# OHIS_FT65E.net
KiCad netlist of a schematic drawn in Altium Designer
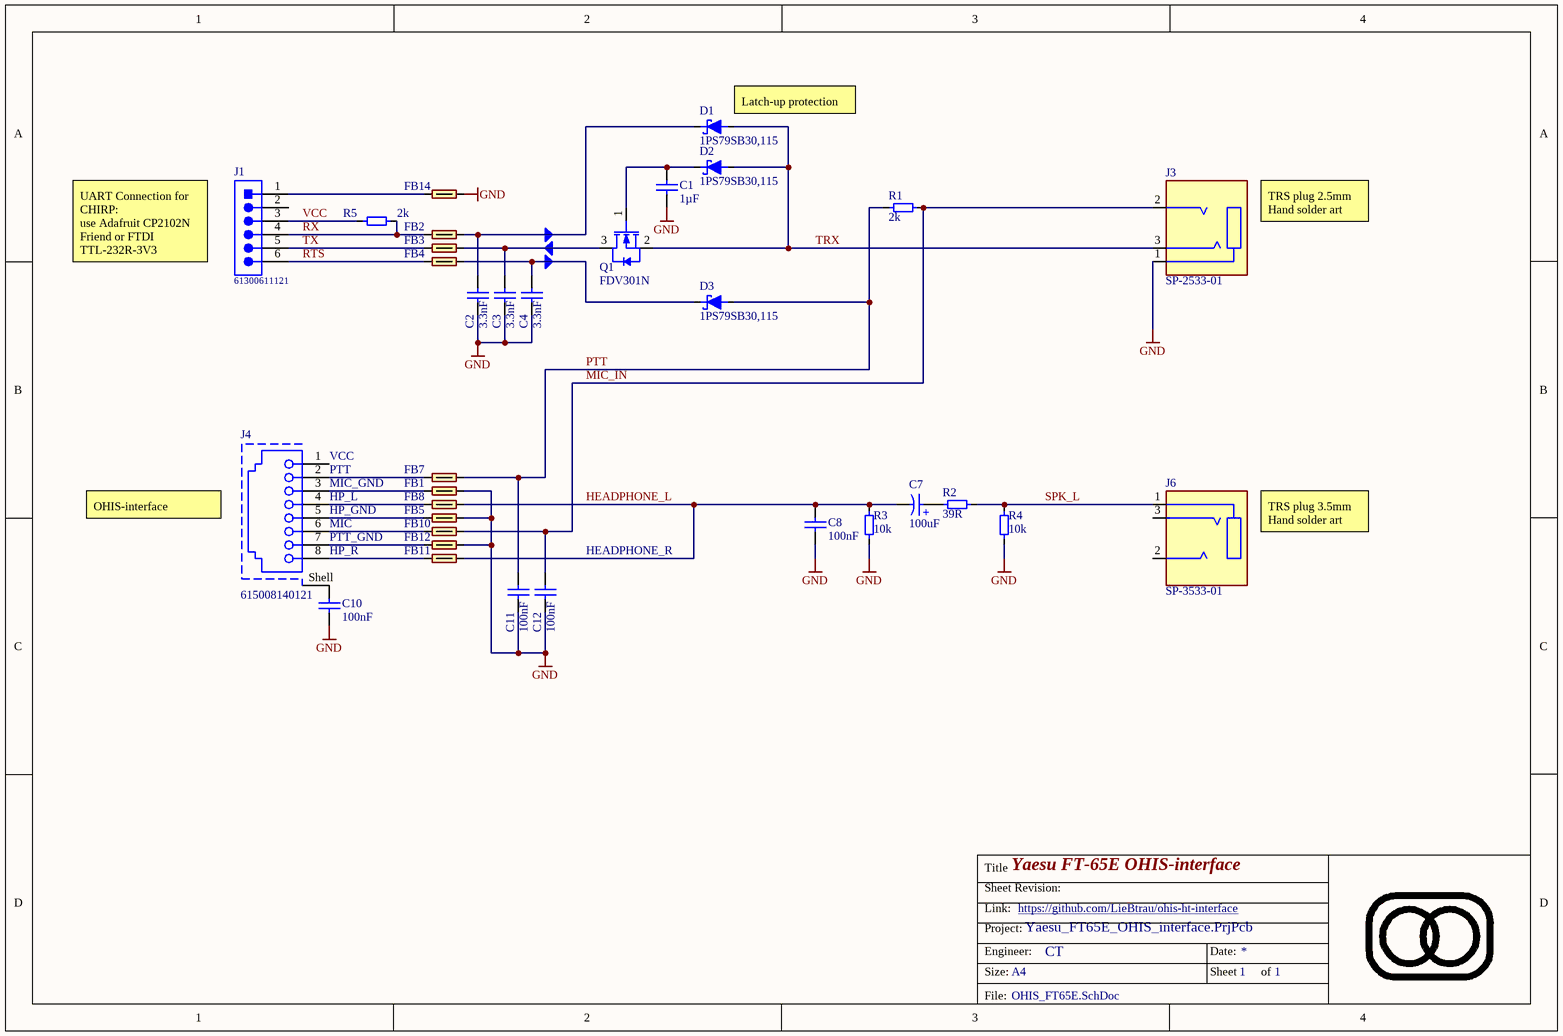
[diagram p0: OHIS_FT65E.SchDoc]

(export (version "E")
  (design (tool "Eeschema 10.0.6"))
  (components
    (comp (ref "C1")
      (value "1µF")
      (footprint "0805-C-N")
      (description "WCAP-CSGP Multilayer Ceramic Chip Capacitor, General Purpose, size 0805, X7R, 1µF, 10VDC")
      (fields (field (name "TOLERANCE") "10%") (field (name "JLCPCB PART #") "C28323"))
      (libsource (lib "7c7 Engineering") (part "CAP-NP-2"))
    )
    (comp (ref "C2")
      (value "3.3nF")
      (footprint "0603-C-N")
      (description "WCAP-CSGP Multilayer Ceramic Chip Capacitor, General Purpose, size 0603, X7R, 3.3nF, 50VDC")
      (fields (field (name "TOLERANCE") "10%") (field (name "Comment") "Capacitor 3.3nF +/-10% 50V X7R 0603"))
      (libsource (lib "7c7 Engineering") (part "CAP-NP-2"))
    )
    (comp (ref "C3")
      (value "3.3nF")
      (footprint "0603-C-N")
      (description "WCAP-CSGP Multilayer Ceramic Chip Capacitor, General Purpose, size 0603, X7R, 3.3nF, 50VDC")
      (fields (field (name "TOLERANCE") "10%") (field (name "Comment") "Capacitor 3.3nF +/-10% 50V X7R 0603"))
      (libsource (lib "7c7 Engineering") (part "CAP-NP-2"))
    )
    (comp (ref "C4")
      (value "3.3nF")
      (footprint "0603-C-N")
      (description "WCAP-CSGP Multilayer Ceramic Chip Capacitor, General Purpose, size 0603, X7R, 3.3nF, 50VDC")
      (fields (field (name "TOLERANCE") "10%") (field (name "Comment") "Capacitor 3.3nF +/-10% 50V X7R 0603"))
      (libsource (lib "7c7 Engineering") (part "CAP-NP-2"))
    )
    (comp (ref "C7")
      (value "865080142007")
      (footprint "WCAP-ASLI_D5H5.5")
      (description "WCAP-ASLI Aluminum Electrolytic Capacitor, V-Chip, D5 x H5.5mm, 100uF, 6.3V")
      (fields (field (name "CAPACITANCE") "100uF") (field (name "MANUFACTURER") "Wurth Elektronik"))
      (libsource (lib "7c7 Engineering") (part "865081763011"))
    )
    (comp (ref "C8")
      (value "100nF")
      (footprint "0603-C-N")
      (description "Capacitor MLCC, General Purpose, size 0603, X7R, 100nF, +/-10%, 50V")
      (fields (field (name "JLCPCB PART #") "C14663") (field (name "TOLERANCE") "10%"))
      (libsource (lib "7c7 Engineering") (part "CAP-NP-2"))
    )
    (comp (ref "C10")
      (value "100nF")
      (footprint "0603-C-N")
      (description "Capacitor MLCC, General Purpose, size 0603, X7R, 100nF, +/-10%, 50V")
      (fields (field (name "JLCPCB PART #") "C14663") (field (name "TOLERANCE") "10%"))
      (libsource (lib "7c7 Engineering") (part "CAP-NP-2"))
    )
    (comp (ref "C11")
      (value "100nF")
      (footprint "0603-C-N")
      (description "Capacitor MLCC, General Purpose, size 0603, X7R, 100nF, +/-10%, 50V")
      (fields (field (name "JLCPCB PART #") "C14663") (field (name "TOLERANCE") "10%"))
      (libsource (lib "7c7 Engineering") (part "CAP-NP-2"))
    )
    (comp (ref "C12")
      (value "100nF")
      (footprint "0603-C-N")
      (description "Capacitor MLCC, General Purpose, size 0603, X7R, 100nF, +/-10%, 50V")
      (fields (field (name "JLCPCB PART #") "C14663") (field (name "TOLERANCE") "10%"))
      (libsource (lib "7c7 Engineering") (part "CAP-NP-2"))
    )
    (comp (ref "D1")
      (value "1PS79SB30,115")
      (footprint "FP-SOD523-MFG")
      (description "VR=40V IF=200mA 20pF")
      (fields (field (name "JLCPCB PART #") "C426690"))
      (libsource (lib "7c7 Engineering") (part "DIODE-SKY-2"))
    )
    (comp (ref "D2")
      (value "1PS79SB30,115")
      (footprint "FP-SOD523-MFG")
      (description "VR=40V IF=200mA 20pF")
      (fields (field (name "JLCPCB PART #") "C426690"))
      (libsource (lib "7c7 Engineering") (part "DIODE-SKY-2"))
    )
    (comp (ref "D3")
      (value "1PS79SB30,115")
      (footprint "FP-SOD523-MFG")
      (description "VR=40V IF=200mA 20pF")
      (fields (field (name "JLCPCB PART #") "C426690"))
      (libsource (lib "7c7 Engineering") (part "DIODE-SKY-2"))
    )
    (comp (ref "FB1")
      (value "742861210")
      (footprint "0603-FB-N")
      (description "Ferrite Beads Multi-Layer 1KOhm 25% 100MHz 50mA 1.8Ohm DCR 0603 T/R")
      (fields (field (name "TOLERANCE") "25%"))
      (libsource (lib "7c7 Engineering") (part "IND_BEAD"))
    )
    (comp (ref "FB2")
      (value "742861210")
      (footprint "0603-FB-N")
      (description "Ferrite Beads Multi-Layer 1KOhm 25% 100MHz 50mA 1.8Ohm DCR 0603 T/R")
      (fields (field (name "TOLERANCE") "25%"))
      (libsource (lib "7c7 Engineering") (part "IND_BEAD"))
    )
    (comp (ref "FB3")
      (value "742861210")
      (footprint "0603-FB-N")
      (description "Ferrite Beads Multi-Layer 1KOhm 25% 100MHz 50mA 1.8Ohm DCR 0603 T/R")
      (fields (field (name "TOLERANCE") "25%"))
      (libsource (lib "7c7 Engineering") (part "IND_BEAD"))
    )
    (comp (ref "FB4")
      (value "742861210")
      (footprint "0603-FB-N")
      (description "Ferrite Beads Multi-Layer 1KOhm 25% 100MHz 50mA 1.8Ohm DCR 0603 T/R")
      (fields (field (name "TOLERANCE") "25%"))
      (libsource (lib "7c7 Engineering") (part "IND_BEAD"))
    )
    (comp (ref "FB5")
      (value "742861210")
      (footprint "0603-FB-N")
      (description "Ferrite Beads Multi-Layer 1KOhm 25% 100MHz 50mA 1.8Ohm DCR 0603 T/R")
      (fields (field (name "TOLERANCE") "25%"))
      (libsource (lib "7c7 Engineering") (part "IND_BEAD"))
    )
    (comp (ref "FB7")
      (value "742861210")
      (footprint "0603-FB-N")
      (description "Ferrite Beads Multi-Layer 1KOhm 25% 100MHz 50mA 1.8Ohm DCR 0603 T/R")
      (fields (field (name "TOLERANCE") "25%"))
      (libsource (lib "7c7 Engineering") (part "IND_BEAD"))
    )
    (comp (ref "FB8")
      (value "742861210")
      (footprint "0603-FB-N")
      (description "Ferrite Beads Multi-Layer 1KOhm 25% 100MHz 50mA 1.8Ohm DCR 0603 T/R")
      (fields (field (name "TOLERANCE") "25%"))
      (libsource (lib "7c7 Engineering") (part "IND_BEAD"))
    )
    (comp (ref "FB10")
      (value "742861210")
      (footprint "0603-FB-N")
      (description "Ferrite Beads Multi-Layer 1KOhm 25% 100MHz 50mA 1.8Ohm DCR 0603 T/R")
      (fields (field (name "TOLERANCE") "25%"))
      (libsource (lib "7c7 Engineering") (part "IND_BEAD"))
    )
    (comp (ref "FB11")
      (value "742861210")
      (footprint "0603-FB-N")
      (description "Ferrite Beads Multi-Layer 1KOhm 25% 100MHz 50mA 1.8Ohm DCR 0603 T/R")
      (fields (field (name "TOLERANCE") "25%"))
      (libsource (lib "7c7 Engineering") (part "IND_BEAD"))
    )
    (comp (ref "FB12")
      (value "742861210")
      (footprint "0603-FB-N")
      (description "Ferrite Beads Multi-Layer 1KOhm 25% 100MHz 50mA 1.8Ohm DCR 0603 T/R")
      (fields (field (name "TOLERANCE") "25%"))
      (libsource (lib "7c7 Engineering") (part "IND_BEAD"))
    )
    (comp (ref "FB14")
      (value "742861210")
      (footprint "0603-FB-N")
      (description "Ferrite Beads Multi-Layer 1KOhm 25% 100MHz 50mA 1.8Ohm DCR 0603 T/R")
      (fields (field (name "TOLERANCE") "25%"))
      (libsource (lib "7c7 Engineering") (part "IND_BEAD"))
    )
    (comp (ref "J1")
      (value "61300611121")
      (footprint "61300611121")
      (description "WR-PHD Pin Header, THT, pitch 2.54mm, Single Row, Vertical, 6p")
      (fields (field (name "MANUFACTURER") "Wurth Elektronik"))
      (libsource (lib "7c7 Engineering") (part "Symbol"))
    )
    (comp (ref "J3")
      (value "SP-2533-01")
      (footprint "SP-2533-01-Footprint-1")
      (description "2.5 mm, Stereo, Overmold, Audio Plug Connector")
      (libsource (lib "7c7 Engineering") (part "CN_AUDIO_JACK_TRS_NO_SWITCH"))
    )
    (comp (ref "J4")
      (value "615008140121")
      (footprint "615008140121")
      (description "WR-MJ Modular Jack THT Horizontal Shielded Front Grounding Post 8P8C Tab Down")
      (fields (field (name "JLCPCB PART #") "C3010555") (field (name "MANUFACTURER") "Wurth Elektronik"))
      (libsource (lib "7c7 Engineering") (part "615108150221R"))
    )
    (comp (ref "J6")
      (value "SP-3533-01")
      (footprint "SP-3533-01-Footprint-1")
      (description "3.5 mm, Stereo, Overmold, Audio Plug Connector")
      (libsource (lib "") (part "CN_AUDIO_JACK_TRS_NO_SWITCH_1"))
    )
    (comp (ref "Q1")
      (value "FDV301N")
      (footprint "SOT-23-3-N")
      (description "Transistor MOSFET N-Ch. 25V 220mA 0, 35W 4Ohm SOT23")
      (fields (field (name "JLCPCB PART #") "C15310"))
      (libsource (lib "7c7 Engineering") (part "NEMOS-GSD-3"))
    )
    (comp (ref "R1")
      (value "2k")
      (footprint "0603-R-N")
      (description "Chip Resistor, Thick Film, General Purpose, 0603, 100mW, 50V, 2 kOhm, +/-1%")
      (fields (field (name "JLCPCB PART #") "C22975") (field (name "TOLERANCE") "1%"))
      (libsource (lib "") (part "RES_1"))
    )
    (comp (ref "R2")
      (value "39R")
      (footprint "0603-R-N")
      (description "SMD Chip Resistor, 39 Ohm, ± 1%, 100 mW, 0603 [1608 Metric], Thick Film, General Purpose")
      (fields (field (name "TOLERANCE") "1%") (field (name "JLCPCB PART #") "C2907161"))
      (libsource (lib "") (part "RES_1"))
    )
    (comp (ref "R3")
      (value "10k")
      (footprint "0603-R-N")
      (description "Chip Resistor, Thick Film, General Purpose, 0603, 100mW, 50V, 10 kOhm, +/-1%")
      (fields (field (name "JLCPCB PART #") "C25804") (field (name "TOLERANCE") "1%"))
      (libsource (lib "7c7 Engineering") (part "RES"))
    )
    (comp (ref "R4")
      (value "10k")
      (footprint "0603-R-N")
      (description "Chip Resistor, Thick Film, General Purpose, 0603, 100mW, 50V, 10 kOhm, +/-1%")
      (fields (field (name "JLCPCB PART #") "C25804") (field (name "TOLERANCE") "1%"))
      (libsource (lib "7c7 Engineering") (part "RES"))
    )
    (comp (ref "R5")
      (value "2k")
      (footprint "0603-R-N")
      (description "Chip Resistor, Thick Film, General Purpose, 0603, 100mW, 50V, 2 kOhm, +/-1%")
      (fields (field (name "JLCPCB PART #") "C22975") (field (name "TOLERANCE") "1%"))
      (libsource (lib "") (part "RES_1"))
    )
  )
  (nets
    (net (code "1") (name "/HEADPHONE_L") (class "Default")
      (node (ref "C7") (pin "2") (pinfunction "N_2") (pintype "passive"))
      (node (ref "C8") (pin "2") (pinfunction "2_2") (pintype "passive"))
      (node (ref "FB11") (pin "2") (pinfunction "2_2") (pintype "passive"))
      (node (ref "FB8") (pin "2") (pinfunction "2_2") (pintype "passive"))
      (node (ref "R3") (pin "2") (pinfunction "2_2") (pintype "passive"))
    )
    (net (code "2") (name "/MIC_IN") (class "Default")
      (node (ref "C12") (pin "2") (pinfunction "2_2") (pintype "passive"))
      (node (ref "FB10") (pin "2") (pinfunction "2_2") (pintype "passive"))
      (node (ref "J3") (pin "2") (pinfunction "2_2") (pintype "passive"))
      (node (ref "R1") (pin "2") (pinfunction "2_2") (pintype "passive"))
    )
    (net (code "3") (name "/PTT") (class "Default")
      (node (ref "C11") (pin "2") (pinfunction "2_2") (pintype "passive"))
      (node (ref "D3") (pin "2") (pinfunction "A_2") (pintype "passive"))
      (node (ref "FB7") (pin "2") (pinfunction "2_2") (pintype "passive"))
      (node (ref "R1") (pin "1") (pinfunction "1_1") (pintype "passive"))
    )
    (net (code "4") (name "/RTS") (class "Default")
      (node (ref "FB4") (pin "1") (pinfunction "1_1") (pintype "passive"))
      (node (ref "J1") (pin "6") (pinfunction "6_6") (pintype "passive"))
    )
    (net (code "5") (name "/RX") (class "Default")
      (node (ref "FB2") (pin "1") (pinfunction "1_1") (pintype "passive"))
      (node (ref "J1") (pin "4") (pinfunction "4_4") (pintype "passive"))
      (node (ref "R5") (pin "2") (pinfunction "2_2") (pintype "passive"))
    )
    (net (code "6") (name "/SPK_L") (class "Default")
      (node (ref "J6") (pin "1") (pinfunction "1_1") (pintype "passive"))
      (node (ref "R2") (pin "2") (pinfunction "2_2") (pintype "passive"))
      (node (ref "R4") (pin "2") (pinfunction "2_2") (pintype "passive"))
    )
    (net (code "7") (name "/TRX") (class "Default")
      (node (ref "D1") (pin "2") (pinfunction "A_2") (pintype "passive"))
      (node (ref "D2") (pin "2") (pinfunction "A_2") (pintype "passive"))
      (node (ref "J3") (pin "3") (pinfunction "3_3") (pintype "passive"))
      (node (ref "Q1") (pin "2") (pinfunction "S_2") (pintype "passive"))
    )
    (net (code "8") (name "/TX") (class "Default")
      (node (ref "FB3") (pin "1") (pinfunction "1_1") (pintype "passive"))
      (node (ref "J1") (pin "5") (pinfunction "5_5") (pintype "passive"))
    )
    (net (code "9") (name "/VCC") (class "Default")
      (node (ref "J1") (pin "3") (pinfunction "3_3") (pintype "passive"))
      (node (ref "R5") (pin "1") (pinfunction "1_1") (pintype "passive"))
    )
    (net (code "10") (name "GND") (class "Default")
      (node (ref "C1") (pin "1") (pinfunction "1_1") (pintype "passive"))
      (node (ref "C10") (pin "1") (pinfunction "1_1") (pintype "passive"))
      (node (ref "C11") (pin "1") (pinfunction "1_1") (pintype "passive"))
      (node (ref "C12") (pin "1") (pinfunction "1_1") (pintype "passive"))
      (node (ref "C2") (pin "1") (pinfunction "1_1") (pintype "passive"))
      (node (ref "C3") (pin "1") (pinfunction "1_1") (pintype "passive"))
      (node (ref "C4") (pin "1") (pinfunction "1_1") (pintype "passive"))
      (node (ref "C8") (pin "1") (pinfunction "1_1") (pintype "passive"))
      (node (ref "FB1") (pin "2") (pinfunction "2_2") (pintype "passive"))
      (node (ref "FB12") (pin "2") (pinfunction "2_2") (pintype "passive"))
      (node (ref "FB14") (pin "2") (pinfunction "2_2") (pintype "passive"))
      (node (ref "FB5") (pin "2") (pinfunction "2_2") (pintype "passive"))
      (node (ref "J3") (pin "1") (pinfunction "1_1") (pintype "passive"))
      (node (ref "R3") (pin "1") (pinfunction "1_1") (pintype "passive"))
      (node (ref "R4") (pin "1") (pinfunction "1_1") (pintype "passive"))
    )
    (net (code "11") (name "Net-(C7-P)") (class "Default")
      (node (ref "C7") (pin "1") (pinfunction "P_1") (pintype "passive"))
      (node (ref "R2") (pin "1") (pinfunction "1_1") (pintype "passive"))
    )
    (net (code "12") (name "Net-(C10-Pad2)") (class "Default")
      (node (ref "C10") (pin "2") (pinfunction "2_2") (pintype "passive"))
      (node (ref "J4") (pin "Shell") (pinfunction "Shell_Shell") (pintype "passive"))
    )
    (net (code "13") (name "Net-(D1-K)") (class "Default")
      (node (ref "C2") (pin "2") (pinfunction "2_2") (pintype "passive"))
      (node (ref "D1") (pin "1") (pinfunction "K_1") (pintype "passive"))
      (node (ref "FB2") (pin "2") (pinfunction "2_2") (pintype "passive"))
    )
    (net (code "14") (name "Net-(D2-K)") (class "Default")
      (node (ref "C1") (pin "2") (pinfunction "2_2") (pintype "passive"))
      (node (ref "D2") (pin "1") (pinfunction "K_1") (pintype "passive"))
      (node (ref "Q1") (pin "1") (pinfunction "G_1") (pintype "passive"))
    )
    (net (code "15") (name "Net-(D3-K)") (class "Default")
      (node (ref "C4") (pin "2") (pinfunction "2_2") (pintype "passive"))
      (node (ref "D3") (pin "1") (pinfunction "K_1") (pintype "passive"))
      (node (ref "FB4") (pin "2") (pinfunction "2_2") (pintype "passive"))
    )
    (net (code "16") (name "Net-(FB1-Pad1)") (class "Default")
      (node (ref "FB1") (pin "1") (pinfunction "1_1") (pintype "passive"))
      (node (ref "J4") (pin "3") (pinfunction "3_3") (pintype "passive"))
    )
    (net (code "17") (name "Net-(FB5-Pad1)") (class "Default")
      (node (ref "FB5") (pin "1") (pinfunction "1_1") (pintype "passive"))
      (node (ref "J4") (pin "5") (pinfunction "5_5") (pintype "passive"))
    )
    (net (code "18") (name "Net-(FB7-Pad1)") (class "Default")
      (node (ref "FB7") (pin "1") (pinfunction "1_1") (pintype "passive"))
      (node (ref "J4") (pin "2") (pinfunction "2_2") (pintype "passive"))
    )
    (net (code "19") (name "Net-(FB8-Pad1)") (class "Default")
      (node (ref "FB8") (pin "1") (pinfunction "1_1") (pintype "passive"))
      (node (ref "J4") (pin "4") (pinfunction "4_4") (pintype "passive"))
    )
    (net (code "20") (name "Net-(FB10-Pad1)") (class "Default")
      (node (ref "FB10") (pin "1") (pinfunction "1_1") (pintype "passive"))
      (node (ref "J4") (pin "6") (pinfunction "6_6") (pintype "passive"))
    )
    (net (code "21") (name "Net-(FB11-Pad1)") (class "Default")
      (node (ref "FB11") (pin "1") (pinfunction "1_1") (pintype "passive"))
      (node (ref "J4") (pin "8") (pinfunction "8_8") (pintype "passive"))
    )
    (net (code "22") (name "Net-(FB12-Pad1)") (class "Default")
      (node (ref "FB12") (pin "1") (pinfunction "1_1") (pintype "passive"))
      (node (ref "J4") (pin "7") (pinfunction "7_7") (pintype "passive"))
    )
    (net (code "23") (name "Net-(FB14-Pad1)") (class "Default")
      (node (ref "FB14") (pin "1") (pinfunction "1_1") (pintype "passive"))
      (node (ref "J1") (pin "1") (pinfunction "1_1") (pintype "passive"))
    )
    (net (code "24") (name "Net-(Q1-D)") (class "Default")
      (node (ref "C3") (pin "2") (pinfunction "2_2") (pintype "passive"))
      (node (ref "FB3") (pin "2") (pinfunction "2_2") (pintype "passive"))
      (node (ref "Q1") (pin "3") (pinfunction "D_3") (pintype "passive"))
    )
    (net (code "25") (name "unconnected-(J1-Pad2)") (class "Default")
      (node (ref "J1") (pin "2") (pinfunction "2_2") (pintype "passive"))
    )
    (net (code "26") (name "unconnected-(J4-Pad1)") (class "Default")
      (node (ref "J4") (pin "1") (pinfunction "1_1") (pintype "passive"))
    )
    (net (code "27") (name "unconnected-(J6-Pad2)") (class "Default")
      (node (ref "J6") (pin "2") (pinfunction "2_2") (pintype "passive"))
    )
    (net (code "28") (name "unconnected-(J6-Pad3)") (class "Default")
      (node (ref "J6") (pin "3") (pinfunction "3_3") (pintype "passive"))
    )
  )
)
